# KeeWatch_External_Attachment.net
KiCad netlist of a schematic drawn in Altium Designer
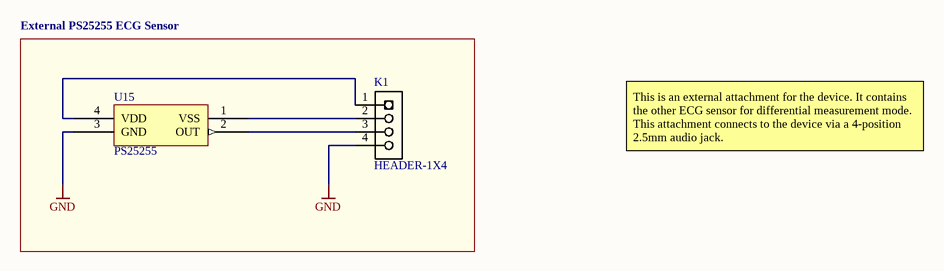
[diagram p0: KeeWatch_External_Attachment.SchDoc]

(export (version "E")
  (design (tool "Eeschema 10.0.6"))
  (components
    (comp (ref "K1")
      (value "HEADER-1X4")
      (footprint "HEADER-1X4")
      (libsource (lib "vh_altium_library") (part "HEADER-1X4"))
    )
    (comp (ref "U15")
      (value "PS25255")
      (footprint "PS25255")
      (description "EPIC Ultra High Impedance ECG Senso")
      (libsource (lib "WATCH") (part "PS25255"))
    )
  )
  (nets
    (net (code "1") (name "GND") (class "Default")
      (node (ref "K1") (pin "4") (pintype "passive"))
      (node (ref "U15") (pin "3") (pinfunction "GND_3") (pintype "passive"))
    )
    (net (code "2") (name "Net-(U15-OUT)") (class "Default")
      (node (ref "K1") (pin "3") (pintype "passive"))
      (node (ref "U15") (pin "2") (pinfunction "OUT_2") (pintype "output"))
    )
    (net (code "3") (name "Net-(U15-VDD)") (class "Default")
      (node (ref "K1") (pin "1") (pintype "passive"))
      (node (ref "U15") (pin "4") (pinfunction "VDD_4") (pintype "passive"))
    )
    (net (code "4") (name "Net-(U15-VSS)") (class "Default")
      (node (ref "K1") (pin "2") (pintype "passive"))
      (node (ref "U15") (pin "1") (pinfunction "VSS_1") (pintype "power_in"))
    )
  )
)
